# KMO_IO_MV3.net
KiCad netlist of a schematic drawn in EAGLE
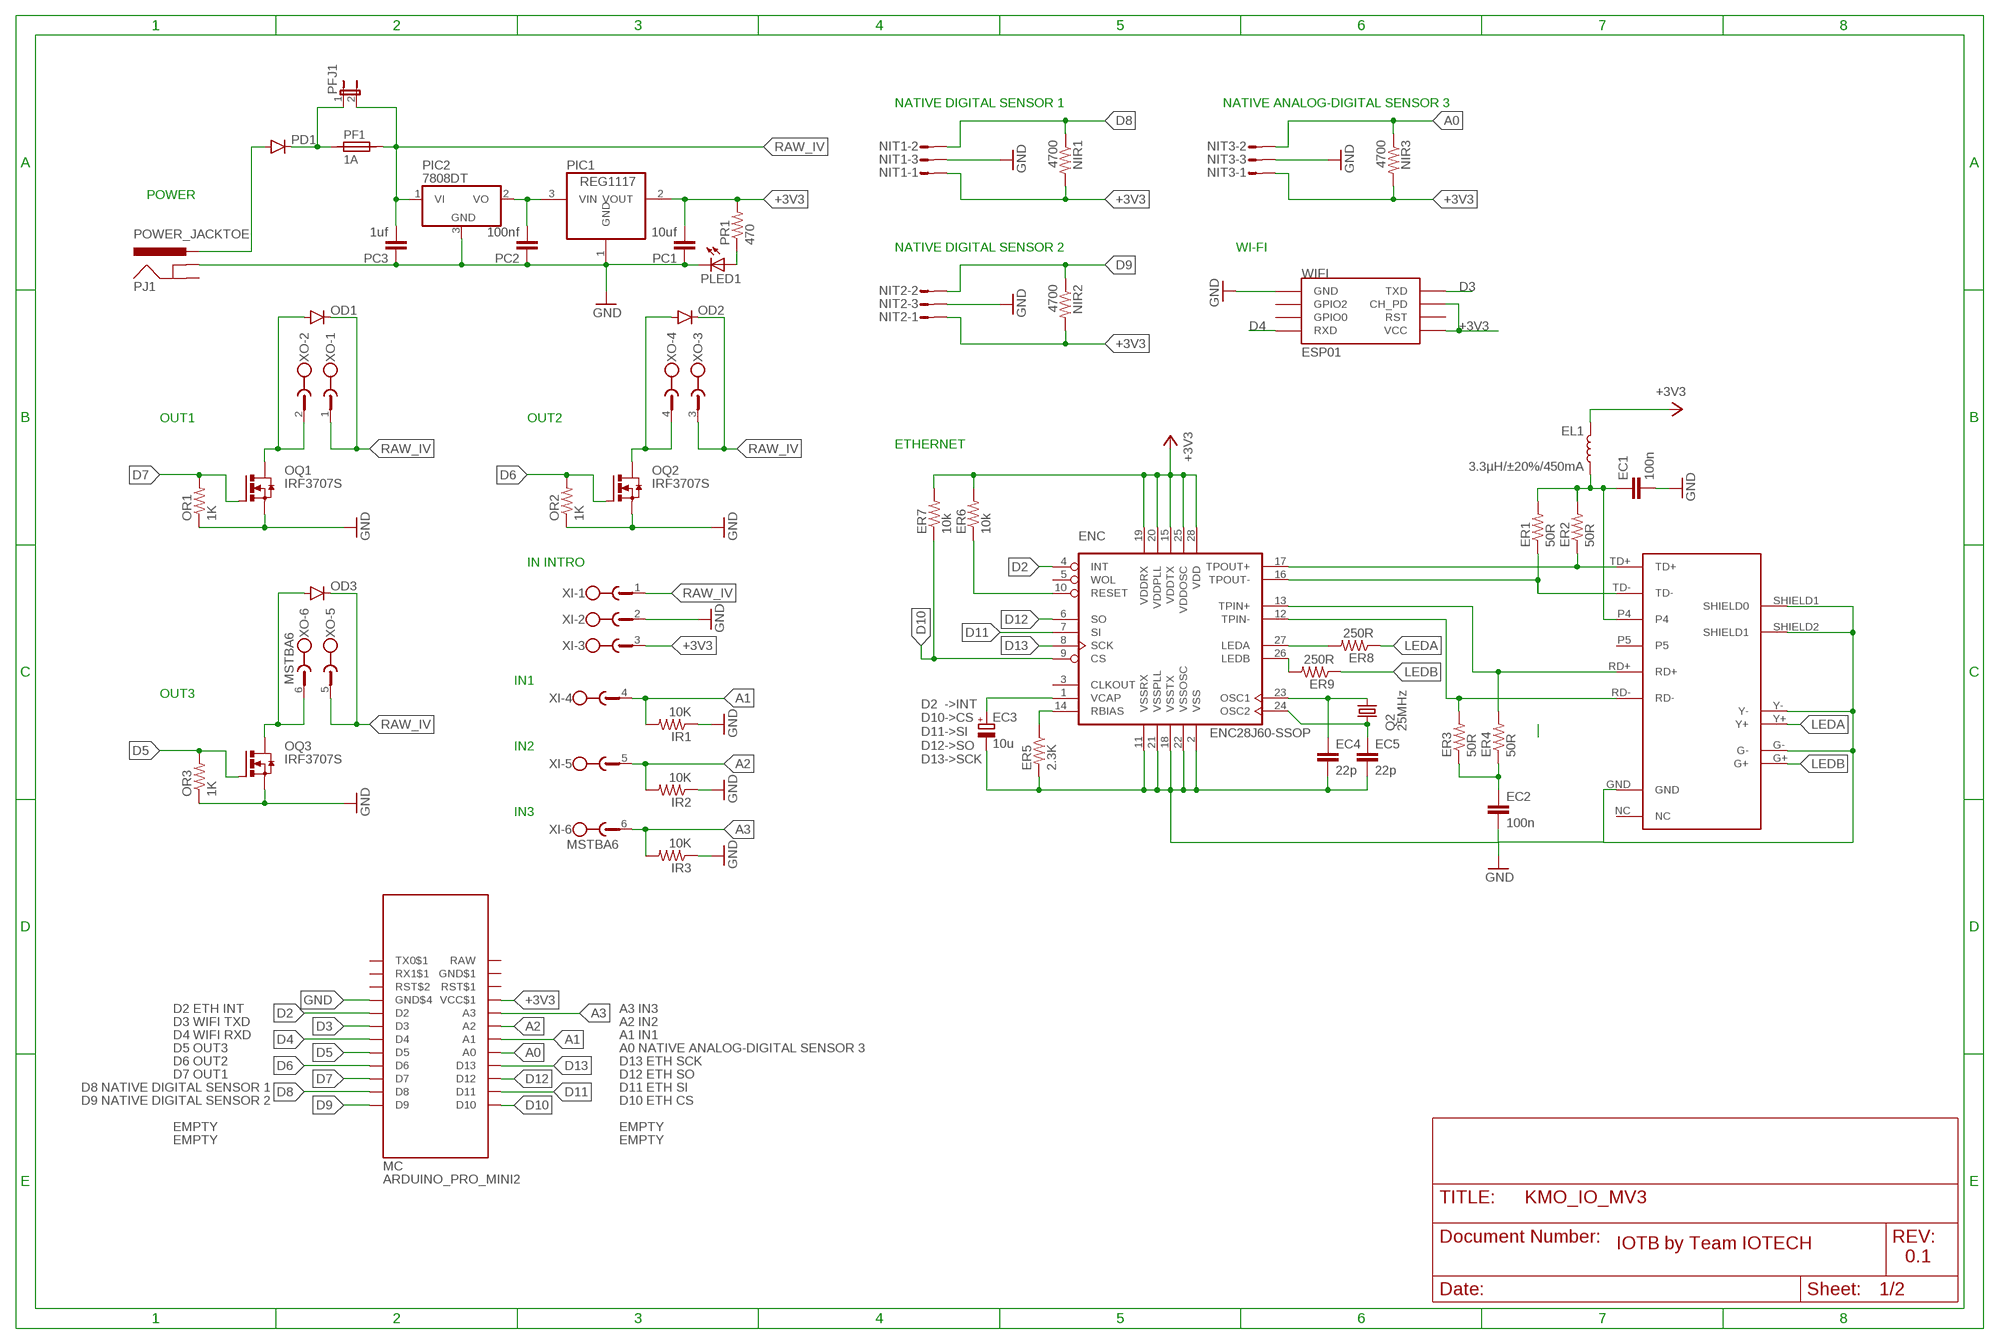
[diagram p0: schematic, sheet 1]
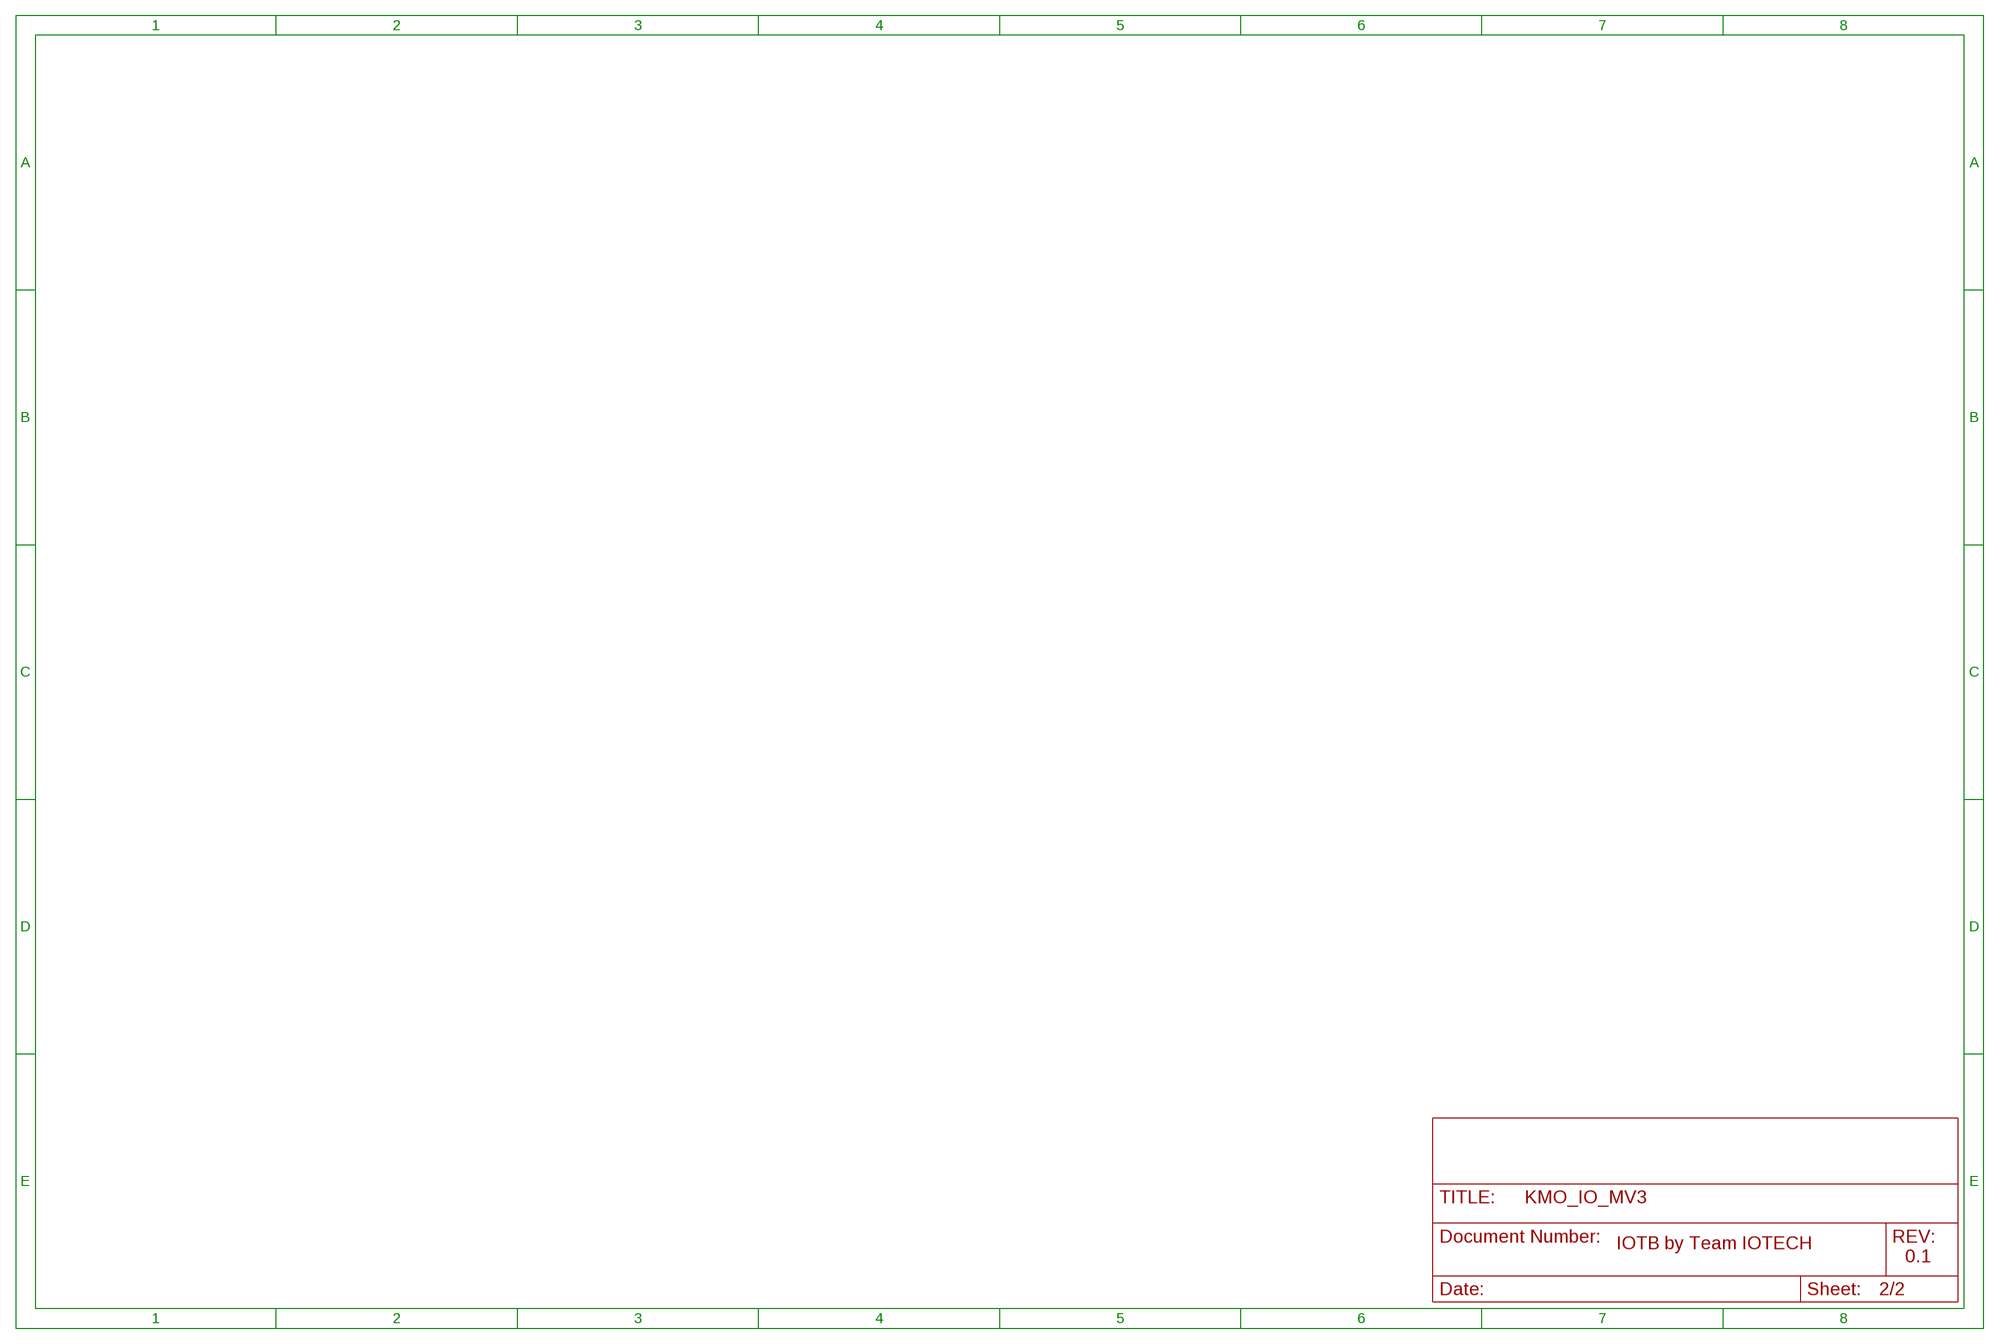
[diagram p1: schematic, sheet 2]

(export (version "E")
  (design (tool "Eeschema 10.0.6"))
  (components
    (comp (ref "EC1")
      (value "100n")
      (footprint "eagle-import:0805")
      (libsource (lib "eagle-import") (part "SparkFun-Passives_CAP0805"))
    )
    (comp (ref "EC2")
      (value "100n")
      (footprint "eagle-import:0805")
      (libsource (lib "eagle-import") (part "SparkFun-Passives_CAP0805"))
    )
    (comp (ref "EC3")
      (value "10u")
      (footprint "eagle-import:SANYO-OSCON_SMD_B6")
      (libsource (lib "eagle-import") (part "CPOL-EUSANYO_SMD_B6"))
    )
    (comp (ref "EC4")
      (value "22p")
      (footprint "eagle-import:0805")
      (libsource (lib "eagle-import") (part "SparkFun-Passives_CAP0805"))
    )
    (comp (ref "EC5")
      (value "22p")
      (footprint "eagle-import:0805")
      (libsource (lib "eagle-import") (part "SparkFun-Passives_CAP0805"))
    )
    (comp (ref "EL1")
      (value "3.3µH/±20%/450mA")
      (footprint "eagle-import:0805")
      (libsource (lib "eagle-import") (part "INDUCTOR-0805-3.3UH"))
    )
    (comp (ref "ENC")
      (value "ENC28J60-SSOP")
      (footprint "eagle-import:SSOP28")
      (libsource (lib "eagle-import") (part "ENC28J60-SSOP"))
    )
    (comp (ref "ER1")
      (value "50R")
      (footprint "eagle-import:0805")
      (libsource (lib "eagle-import") (part "RESISTOR0805-RES"))
    )
    (comp (ref "ER2")
      (value "50R")
      (footprint "eagle-import:0805")
      (libsource (lib "eagle-import") (part "RESISTOR0805-RES"))
    )
    (comp (ref "ER3")
      (value "50R")
      (footprint "eagle-import:0805")
      (libsource (lib "eagle-import") (part "RESISTOR0805-RES"))
    )
    (comp (ref "ER4")
      (value "50R")
      (footprint "eagle-import:0805")
      (libsource (lib "eagle-import") (part "RESISTOR0805-RES"))
    )
    (comp (ref "ER5")
      (value "2.3K")
      (footprint "eagle-import:0805")
      (libsource (lib "eagle-import") (part "RESISTOR0805-RES"))
    )
    (comp (ref "ER6")
      (value "10k")
      (footprint "eagle-import:0805")
      (libsource (lib "eagle-import") (part "RESISTOR0805-RES"))
    )
    (comp (ref "ER7")
      (value "10k")
      (footprint "eagle-import:0805")
      (libsource (lib "eagle-import") (part "RESISTOR0805-RES"))
    )
    (comp (ref "ER8")
      (value "250R")
      (footprint "eagle-import:0805")
      (libsource (lib "eagle-import") (part "RESISTOR0805-RES"))
    )
    (comp (ref "ER9")
      (value "250R")
      (footprint "eagle-import:0805")
      (libsource (lib "eagle-import") (part "RESISTOR0805-RES"))
    )
    (comp (ref "IR1")
      (value "10K")
      (footprint "eagle-import:0805")
      (libsource (lib "eagle-import") (part "RESISTOR0805-RES"))
    )
    (comp (ref "IR2")
      (value "10K")
      (footprint "eagle-import:0805")
      (libsource (lib "eagle-import") (part "RESISTOR0805-RES"))
    )
    (comp (ref "IR3")
      (value "10K")
      (footprint "eagle-import:0805")
      (libsource (lib "eagle-import") (part "RESISTOR0805-RES"))
    )
    (comp (ref "MC")
      (value "ARDUINO_PRO_MINI2")
      (footprint "eagle-import:ARDUINO_PRO_MINI2")
      (libsource (lib "eagle-import") (part "ARDUINO_PRO_MINI2"))
    )
    (comp (ref "NIR1")
      (value "4700")
      (footprint "eagle-import:0805")
      (libsource (lib "eagle-import") (part "RESISTOR0805-RES"))
    )
    (comp (ref "NIR2")
      (value "4700")
      (footprint "eagle-import:0805")
      (libsource (lib "eagle-import") (part "RESISTOR0805-RES"))
    )
    (comp (ref "NIR3")
      (value "4700")
      (footprint "eagle-import:0805")
      (libsource (lib "eagle-import") (part "RESISTOR0805-RES"))
    )
    (comp (ref "NIT1")
      (value "S03P")
      (footprint "eagle-import:S03P")
      (libsource (lib "eagle-import") (part "S03P"))
    )
    (comp (ref "NIT2")
      (value "S03P")
      (footprint "eagle-import:S03P")
      (libsource (lib "eagle-import") (part "S03P"))
    )
    (comp (ref "NIT3")
      (value "S03P")
      (footprint "eagle-import:S03P")
      (libsource (lib "eagle-import") (part "S03P"))
    )
    (comp (ref "OD1")
      (value "DIODESMA")
      (footprint "eagle-import:SMA-DIODE")
      (libsource (lib "eagle-import") (part "DIODESMA"))
    )
    (comp (ref "OD2")
      (value "DIODESMA")
      (footprint "eagle-import:SMA-DIODE")
      (libsource (lib "eagle-import") (part "DIODESMA"))
    )
    (comp (ref "OD3")
      (value "DIODESMA")
      (footprint "eagle-import:SMA-DIODE")
      (libsource (lib "eagle-import") (part "DIODESMA"))
    )
    (comp (ref "OQ1")
      (value "IRF3707S")
      (footprint "eagle-import:D2PACK")
      (libsource (lib "eagle-import") (part "IRF3704S"))
    )
    (comp (ref "OQ2")
      (value "IRF3707S")
      (footprint "eagle-import:D2PACK")
      (libsource (lib "eagle-import") (part "IRF3704S"))
    )
    (comp (ref "OQ3")
      (value "IRF3707S")
      (footprint "eagle-import:D2PACK")
      (libsource (lib "eagle-import") (part "IRF3704S"))
    )
    (comp (ref "OR1")
      (value "1K")
      (footprint "eagle-import:0805")
      (libsource (lib "eagle-import") (part "RESISTOR0805-RES"))
    )
    (comp (ref "OR2")
      (value "1K")
      (footprint "eagle-import:0805")
      (libsource (lib "eagle-import") (part "RESISTOR0805-RES"))
    )
    (comp (ref "OR3")
      (value "1K")
      (footprint "eagle-import:0805")
      (libsource (lib "eagle-import") (part "RESISTOR0805-RES"))
    )
    (comp (ref "PC1")
      (value "10uf")
      (footprint "eagle-import:0805")
      (libsource (lib "eagle-import") (part "CAP0805"))
    )
    (comp (ref "PC2")
      (value "100nf")
      (footprint "eagle-import:0805")
      (libsource (lib "eagle-import") (part "CAP0805"))
    )
    (comp (ref "PC3")
      (value "1uf")
      (footprint "eagle-import:0805")
      (libsource (lib "eagle-import") (part "CAP0805"))
    )
    (comp (ref "PD1")
      (value "DIODESMA")
      (footprint "eagle-import:SMA-DIODE")
      (libsource (lib "eagle-import") (part "DIODESMA"))
    )
    (comp (ref "PF1")
      (value "1A")
      (footprint "eagle-import:1820")
      (libsource (lib "eagle-import") (part "SIBA194600"))
    )
    (comp (ref "PFJ1")
      (value "JP1E")
      (footprint "eagle-import:JP1")
      (libsource (lib "eagle-import") (part "JP1E"))
    )
    (comp (ref "PIC1")
      (value "REG1117")
      (footprint "eagle-import:SOT223")
      (libsource (lib "eagle-import") (part "REG1117"))
    )
    (comp (ref "PIC2")
      (value "7808DT")
      (footprint "eagle-import:TO252")
      (libsource (lib "eagle-import") (part "78DT08"))
    )
    (comp (ref "PJ1")
      (value "POWER_JACKTOE")
      (footprint "eagle-import:POWER_JACK_SMD_OVERPASTE_TOE")
      (libsource (lib "eagle-import") (part "POWER_JACKTOE"))
    )
    (comp (ref "PLED1")
      (value "LEDCHIP-LED0805")
      (footprint "eagle-import:CHIP-LED0805")
      (libsource (lib "eagle-import") (part "LEDCHIP-LED0805"))
    )
    (comp (ref "PR1")
      (value "470")
      (footprint "eagle-import:0805")
      (libsource (lib "eagle-import") (part "RESISTOR0805-RES"))
    )
    (comp (ref "Q2")
      (value "25MHz")
      (footprint "eagle-import:HC49_S")
      (libsource (lib "eagle-import") (part "CRYSTALHC49S"))
    )
    (comp (ref "U$2")
      (value "HR911105A")
      (footprint "eagle-import:RJ45")
      (libsource (lib "eagle-import") (part "HR911105A"))
    )
    (comp (ref "WIFI")
      (value "ESP01")
      (footprint "eagle-import:ESP01")
      (libsource (lib "eagle-import") (part "ESP01"))
    )
    (comp (ref "XI")
      (value "MSTBA6")
      (footprint "eagle-import:MSTBA6")
      (fields (field (name "MF") "FARNELL") (field (name "MPN") "1757284"))
      (libsource (lib "eagle-import") (part "MSTBA6"))
    )
    (comp (ref "XO")
      (value "MSTBA6")
      (footprint "eagle-import:MSTBA6")
      (fields (field (name "MF") "FARNELL") (field (name "MPN") "1757284"))
      (libsource (lib "eagle-import") (part "MSTBA6"))
    )
  )
  (nets
    (net (code "1") (name "+3V3") (class "Default")
      (node (ref "EL1") (pin "1") (pinfunction "1_1") (pintype "passive"))
      (node (ref "ENC") (pin "15") (pinfunction "VDDTX_15") (pintype "power_in"))
      (node (ref "ENC") (pin "19") (pinfunction "VDDRX_19") (pintype "power_in"))
      (node (ref "ENC") (pin "20") (pinfunction "VDDPLL_20") (pintype "power_in"))
      (node (ref "ENC") (pin "25") (pinfunction "VDDOSC_25") (pintype "power_in"))
      (node (ref "ENC") (pin "28") (pinfunction "VDD_28") (pintype "power_in"))
      (node (ref "ER6") (pin "2") (pinfunction "2_2") (pintype "passive"))
      (node (ref "ER7") (pin "2") (pinfunction "2_2") (pintype "passive"))
      (node (ref "MC") (pin "VCC$1") (pinfunction "VCC$1_VCC$1") (pintype "power_in"))
      (node (ref "NIR1") (pin "2") (pinfunction "2_2") (pintype "passive"))
      (node (ref "NIR2") (pin "2") (pinfunction "2_2") (pintype "passive"))
      (node (ref "NIR3") (pin "2") (pinfunction "2_2") (pintype "passive"))
      (node (ref "NIT1") (pin "1") (pinfunction "S_1") (pintype "passive"))
      (node (ref "NIT2") (pin "1") (pinfunction "S_1") (pintype "passive"))
      (node (ref "NIT3") (pin "1") (pinfunction "S_1") (pintype "passive"))
      (node (ref "PC1") (pin "2") (pinfunction "2_2") (pintype "passive"))
      (node (ref "PIC1") (pin "2") (pinfunction "VOUT_2") (pintype "output"))
      (node (ref "PR1") (pin "2") (pinfunction "2_2") (pintype "passive"))
      (node (ref "WIFI") (pin "CH_PD") (pinfunction "CH_PD_CH_PD") (pintype "bidirectional"))
      (node (ref "WIFI") (pin "VCC") (pinfunction "VCC_VCC") (pintype "bidirectional"))
      (node (ref "XI") (pin "3") (pinfunction "1_3") (pintype "passive"))
    )
    (net (code "2") (name "A0") (class "Default")
      (node (ref "MC") (pin "A0") (pinfunction "A0_A0") (pintype "bidirectional"))
      (node (ref "NIR3") (pin "1") (pinfunction "1_1") (pintype "passive"))
      (node (ref "NIT3") (pin "2") (pinfunction "S_2") (pintype "passive"))
    )
    (net (code "3") (name "A1") (class "Default")
      (node (ref "IR1") (pin "2") (pinfunction "2_2") (pintype "passive"))
      (node (ref "MC") (pin "A1") (pinfunction "A1_A1") (pintype "bidirectional"))
      (node (ref "XI") (pin "4") (pinfunction "1_4") (pintype "passive"))
    )
    (net (code "4") (name "A2") (class "Default")
      (node (ref "IR2") (pin "2") (pinfunction "2_2") (pintype "passive"))
      (node (ref "MC") (pin "A2") (pinfunction "A2_A2") (pintype "bidirectional"))
      (node (ref "XI") (pin "5") (pinfunction "1_5") (pintype "passive"))
    )
    (net (code "5") (name "A3") (class "Default")
      (node (ref "IR3") (pin "2") (pinfunction "2_2") (pintype "passive"))
      (node (ref "MC") (pin "A3") (pinfunction "A3_A3") (pintype "bidirectional"))
      (node (ref "XI") (pin "6") (pinfunction "1_6") (pintype "passive"))
    )
    (net (code "6") (name "D2") (class "Default")
      (node (ref "ENC") (pin "4") (pinfunction "INT_4") (pintype "output"))
      (node (ref "MC") (pin "D2") (pinfunction "D2_D2") (pintype "bidirectional"))
    )
    (net (code "7") (name "D3") (class "Default")
      (node (ref "MC") (pin "D3") (pinfunction "D3_D3") (pintype "bidirectional"))
      (node (ref "WIFI") (pin "TX") (pinfunction "TXD_TX") (pintype "bidirectional"))
    )
    (net (code "8") (name "D4") (class "Default")
      (node (ref "MC") (pin "D4") (pinfunction "D4_D4") (pintype "bidirectional"))
      (node (ref "WIFI") (pin "RX") (pinfunction "RXD_RX") (pintype "bidirectional"))
    )
    (net (code "9") (name "D5") (class "Default")
      (node (ref "MC") (pin "D5") (pinfunction "D5_D5") (pintype "bidirectional"))
      (node (ref "OQ3") (pin "1") (pinfunction "G_1") (pintype "passive"))
      (node (ref "OR3") (pin "2") (pinfunction "2_2") (pintype "passive"))
    )
    (net (code "10") (name "D6") (class "Default")
      (node (ref "MC") (pin "D6") (pinfunction "D6_D6") (pintype "bidirectional"))
      (node (ref "OQ2") (pin "1") (pinfunction "G_1") (pintype "passive"))
      (node (ref "OR2") (pin "2") (pinfunction "2_2") (pintype "passive"))
    )
    (net (code "11") (name "D7") (class "Default")
      (node (ref "MC") (pin "D7") (pinfunction "D7_D7") (pintype "bidirectional"))
      (node (ref "OQ1") (pin "1") (pinfunction "G_1") (pintype "passive"))
      (node (ref "OR1") (pin "2") (pinfunction "2_2") (pintype "passive"))
    )
    (net (code "12") (name "D8") (class "Default")
      (node (ref "MC") (pin "D8") (pinfunction "D8_D8") (pintype "bidirectional"))
      (node (ref "NIR1") (pin "1") (pinfunction "1_1") (pintype "passive"))
      (node (ref "NIT1") (pin "2") (pinfunction "S_2") (pintype "passive"))
    )
    (net (code "13") (name "D9") (class "Default")
      (node (ref "MC") (pin "D9") (pinfunction "D9_D9") (pintype "bidirectional"))
      (node (ref "NIR2") (pin "1") (pinfunction "1_1") (pintype "passive"))
      (node (ref "NIT2") (pin "2") (pinfunction "S_2") (pintype "passive"))
    )
    (net (code "14") (name "D10") (class "Default")
      (node (ref "ENC") (pin "9") (pinfunction "CS_9") (pintype "input"))
      (node (ref "ER7") (pin "1") (pinfunction "1_1") (pintype "passive"))
      (node (ref "MC") (pin "D10") (pinfunction "D10_D10") (pintype "bidirectional"))
    )
    (net (code "15") (name "D11") (class "Default")
      (node (ref "ENC") (pin "7") (pinfunction "SI_7") (pintype "input"))
      (node (ref "MC") (pin "D11") (pinfunction "D11_D11") (pintype "bidirectional"))
    )
    (net (code "16") (name "D12") (class "Default")
      (node (ref "ENC") (pin "6") (pinfunction "SO_6") (pintype "output"))
      (node (ref "MC") (pin "D12") (pinfunction "D12_D12") (pintype "bidirectional"))
    )
    (net (code "17") (name "D13") (class "Default")
      (node (ref "ENC") (pin "8") (pinfunction "SCK_8") (pintype "input"))
      (node (ref "MC") (pin "D13") (pinfunction "D13_D13") (pintype "bidirectional"))
    )
    (net (code "18") (name "GND") (class "Default")
      (node (ref "EC1") (pin "2") (pinfunction "2_2") (pintype "passive"))
      (node (ref "EC2") (pin "2") (pinfunction "2_2") (pintype "passive"))
      (node (ref "EC3") (pin "-") (pinfunction "-_-") (pintype "passive"))
      (node (ref "EC4") (pin "2") (pinfunction "2_2") (pintype "passive"))
      (node (ref "EC5") (pin "2") (pinfunction "2_2") (pintype "passive"))
      (node (ref "ENC") (pin "11") (pinfunction "VSSRX_11") (pintype "power_in"))
      (node (ref "ENC") (pin "18") (pinfunction "VSSTX_18") (pintype "power_in"))
      (node (ref "ENC") (pin "2") (pinfunction "VSS_2") (pintype "power_in"))
      (node (ref "ENC") (pin "21") (pinfunction "VSSPLL_21") (pintype "power_in"))
      (node (ref "ENC") (pin "22") (pinfunction "VSSOSC_22") (pintype "power_in"))
      (node (ref "ER5") (pin "2") (pinfunction "2_2") (pintype "passive"))
      (node (ref "IR1") (pin "1") (pinfunction "1_1") (pintype "passive"))
      (node (ref "IR2") (pin "1") (pinfunction "1_1") (pintype "passive"))
      (node (ref "IR3") (pin "1") (pinfunction "1_1") (pintype "passive"))
      (node (ref "MC") (pin "GND$4") (pinfunction "GND$4_GND$4") (pintype "power_in"))
      (node (ref "NIT1") (pin "3") (pinfunction "S_3") (pintype "passive"))
      (node (ref "NIT2") (pin "3") (pinfunction "S_3") (pintype "passive"))
      (node (ref "NIT3") (pin "3") (pinfunction "S_3") (pintype "passive"))
      (node (ref "OQ1") (pin "3") (pinfunction "S_3") (pintype "passive"))
      (node (ref "OQ2") (pin "3") (pinfunction "S_3") (pintype "passive"))
      (node (ref "OQ3") (pin "3") (pinfunction "S_3") (pintype "passive"))
      (node (ref "OR1") (pin "1") (pinfunction "1_1") (pintype "passive"))
      (node (ref "OR2") (pin "1") (pinfunction "1_1") (pintype "passive"))
      (node (ref "OR3") (pin "1") (pinfunction "1_1") (pintype "passive"))
      (node (ref "PC1") (pin "1") (pinfunction "1_1") (pintype "passive"))
      (node (ref "PC2") (pin "1") (pinfunction "1_1") (pintype "passive"))
      (node (ref "PC3") (pin "1") (pinfunction "1_1") (pintype "passive"))
      (node (ref "PIC1") (pin "1") (pinfunction "GND_1") (pintype "power_in"))
      (node (ref "PIC2") (pin "3") (pinfunction "GND_3") (pintype "passive"))
      (node (ref "PJ1") (pin "GND") (pinfunction "GNDBREAK_GND") (pintype "bidirectional"))
      (node (ref "PLED1") (pin "C") (pinfunction "C_C") (pintype "passive"))
      (node (ref "U$2") (pin "G-") (pinfunction "G-_G-") (pintype "bidirectional"))
      (node (ref "U$2") (pin "GND") (pinfunction "GND_GND") (pintype "bidirectional"))
      (node (ref "U$2") (pin "SHIELD1") (pinfunction "SHIELD0_SHIELD1") (pintype "bidirectional"))
      (node (ref "U$2") (pin "SHIELD2") (pinfunction "SHIELD1_SHIELD2") (pintype "bidirectional"))
      (node (ref "U$2") (pin "Y-") (pinfunction "Y-_Y-") (pintype "bidirectional"))
      (node (ref "WIFI") (pin "GND") (pinfunction "GND_GND") (pintype "bidirectional"))
      (node (ref "XI") (pin "2") (pinfunction "1_2") (pintype "passive"))
    )
    (net (code "19") (name "GND$1") (class "Default")
      (node (ref "MC") (pin "GDN$1") (pinfunction "GND$1_GDN$1") (pintype "power_in"))
    )
    (net (code "20") (name "LEDA") (class "Default")
      (node (ref "ER8") (pin "1") (pinfunction "1_1") (pintype "passive"))
      (node (ref "U$2") (pin "Y+") (pinfunction "Y+_Y+") (pintype "bidirectional"))
    )
    (net (code "21") (name "LEDB") (class "Default")
      (node (ref "ER9") (pin "1") (pinfunction "1_1") (pintype "passive"))
      (node (ref "U$2") (pin "G+") (pinfunction "G+_G+") (pintype "bidirectional"))
    )
    (net (code "22") (name "Net-(EC1-Pad1)") (class "Default")
      (node (ref "EC1") (pin "1") (pinfunction "1_1") (pintype "passive"))
      (node (ref "EL1") (pin "2") (pinfunction "2_2") (pintype "passive"))
      (node (ref "ER1") (pin "2") (pinfunction "2_2") (pintype "passive"))
      (node (ref "ER2") (pin "2") (pinfunction "2_2") (pintype "passive"))
      (node (ref "U$2") (pin "P4") (pinfunction "P4_P4") (pintype "bidirectional"))
    )
    (net (code "23") (name "Net-(EC2-Pad1)") (class "Default")
      (node (ref "EC2") (pin "1") (pinfunction "1_1") (pintype "passive"))
      (node (ref "ER3") (pin "1") (pinfunction "1_1") (pintype "passive"))
      (node (ref "ER4") (pin "1") (pinfunction "1_1") (pintype "passive"))
    )
    (net (code "24") (name "Net-(ENC-LEDA)") (class "Default")
      (node (ref "ENC") (pin "27") (pinfunction "LEDA_27") (pintype "output"))
      (node (ref "ER8") (pin "2") (pinfunction "2_2") (pintype "passive"))
    )
    (net (code "25") (name "Net-(ENC-LEDB)") (class "Default")
      (node (ref "ENC") (pin "26") (pinfunction "LEDB_26") (pintype "output"))
      (node (ref "ER9") (pin "2") (pinfunction "2_2") (pintype "passive"))
    )
    (net (code "26") (name "Net-(ENC-OSC1)") (class "Default")
      (node (ref "EC4") (pin "1") (pinfunction "1_1") (pintype "passive"))
      (node (ref "ENC") (pin "23") (pinfunction "OSC1_23") (pintype "input"))
      (node (ref "Q2") (pin "2") (pinfunction "2_2") (pintype "passive"))
    )
    (net (code "27") (name "Net-(ENC-OSC2)") (class "Default")
      (node (ref "EC5") (pin "1") (pinfunction "1_1") (pintype "passive"))
      (node (ref "ENC") (pin "24") (pinfunction "OSC2_24") (pintype "output"))
      (node (ref "Q2") (pin "1") (pinfunction "1_1") (pintype "passive"))
    )
    (net (code "28") (name "Net-(ENC-RBIAS)") (class "Default")
      (node (ref "ENC") (pin "14") (pinfunction "RBIAS_14") (pintype "passive"))
      (node (ref "ER5") (pin "1") (pinfunction "1_1") (pintype "passive"))
    )
    (net (code "29") (name "Net-(ENC-RESET)") (class "Default")
      (node (ref "ENC") (pin "10") (pinfunction "RESET_10") (pintype "input"))
      (node (ref "ER6") (pin "1") (pinfunction "1_1") (pintype "passive"))
    )
    (net (code "30") (name "Net-(ENC-TPIN+)") (class "Default")
      (node (ref "ENC") (pin "13") (pinfunction "TPIN+_13") (pintype "input"))
      (node (ref "ER4") (pin "2") (pinfunction "2_2") (pintype "passive"))
      (node (ref "U$2") (pin "RD+") (pinfunction "RD+_RD+") (pintype "bidirectional"))
    )
    (net (code "31") (name "Net-(ENC-TPIN-)") (class "Default")
      (node (ref "ENC") (pin "12") (pinfunction "TPIN-_12") (pintype "input"))
      (node (ref "ER3") (pin "2") (pinfunction "2_2") (pintype "passive"))
      (node (ref "U$2") (pin "RD-") (pinfunction "RD-_RD-") (pintype "bidirectional"))
    )
    (net (code "32") (name "Net-(ENC-TPOUT+)") (class "Default")
      (node (ref "ENC") (pin "17") (pinfunction "TPOUT+_17") (pintype "output"))
      (node (ref "ER2") (pin "1") (pinfunction "1_1") (pintype "passive"))
      (node (ref "U$2") (pin "TD+") (pinfunction "TD+_TD+") (pintype "bidirectional"))
    )
    (net (code "33") (name "Net-(ENC-TPOUT-)") (class "Default")
      (node (ref "ENC") (pin "16") (pinfunction "TPOUT-_16") (pintype "output"))
      (node (ref "ER1") (pin "1") (pinfunction "1_1") (pintype "passive"))
      (node (ref "U$2") (pin "TD-") (pinfunction "TD-_TD-") (pintype "bidirectional"))
    )
    (net (code "34") (name "Net-(ENC-VCAP)") (class "Default")
      (node (ref "EC3") (pin "+") (pinfunction "+_+") (pintype "passive"))
      (node (ref "ENC") (pin "1") (pinfunction "VCAP_1") (pintype "power_in"))
    )
    (net (code "35") (name "Net-(OQ1-D)") (class "Default")
      (node (ref "OD1") (pin "A") (pinfunction "A_A") (pintype "passive"))
      (node (ref "OQ1") (pin "2") (pinfunction "D_2") (pintype "passive"))
      (node (ref "XO") (pin "2") (pinfunction "1_2") (pintype "passive"))
    )
    (net (code "36") (name "Net-(OQ2-D)") (class "Default")
      (node (ref "OD2") (pin "A") (pinfunction "A_A") (pintype "passive"))
      (node (ref "OQ2") (pin "2") (pinfunction "D_2") (pintype "passive"))
      (node (ref "XO") (pin "4") (pinfunction "1_4") (pintype "passive"))
    )
    (net (code "37") (name "Net-(OQ3-D)") (class "Default")
      (node (ref "OD3") (pin "A") (pinfunction "A_A") (pintype "passive"))
      (node (ref "OQ3") (pin "2") (pinfunction "D_2") (pintype "passive"))
      (node (ref "XO") (pin "6") (pinfunction "1_6") (pintype "passive"))
    )
    (net (code "38") (name "Net-(PD1-PadC)") (class "Default")
      (node (ref "PD1") (pin "C") (pinfunction "C_C") (pintype "passive"))
      (node (ref "PF1") (pin "1") (pinfunction "1_1") (pintype "passive"))
      (node (ref "PFJ1") (pin "1") (pinfunction "1_1") (pintype "passive"))
    )
    (net (code "39") (name "Net-(PIC1-VIN)") (class "Default")
      (node (ref "PC2") (pin "2") (pinfunction "2_2") (pintype "passive"))
      (node (ref "PIC1") (pin "3") (pinfunction "VIN_3") (pintype "input"))
      (node (ref "PIC2") (pin "2") (pinfunction "VO_2") (pintype "passive"))
    )
    (net (code "40") (name "Net-(PJ1-PWR)") (class "Default")
      (node (ref "PD1") (pin "A") (pinfunction "A_A") (pintype "passive"))
      (node (ref "PJ1") (pin "VIN0") (pinfunction "PWR_VIN0") (pintype "bidirectional"))
    )
    (net (code "41") (name "Net-(PLED1-PadA)") (class "Default")
      (node (ref "PLED1") (pin "A") (pinfunction "A_A") (pintype "passive"))
      (node (ref "PR1") (pin "1") (pinfunction "1_1") (pintype "passive"))
    )
    (net (code "42") (name "RAW") (class "Default")
      (node (ref "MC") (pin "RAW") (pinfunction "RAW_RAW") (pintype "power_in"))
    )
    (net (code "43") (name "RAW_IV") (class "Default")
      (node (ref "OD1") (pin "C") (pinfunction "C_C") (pintype "passive"))
      (node (ref "OD2") (pin "C") (pinfunction "C_C") (pintype "passive"))
      (node (ref "OD3") (pin "C") (pinfunction "C_C") (pintype "passive"))
      (node (ref "PC3") (pin "2") (pinfunction "2_2") (pintype "passive"))
      (node (ref "PF1") (pin "2") (pinfunction "2_2") (pintype "passive"))
      (node (ref "PFJ1") (pin "2") (pinfunction "2_2") (pintype "passive"))
      (node (ref "PIC2") (pin "1") (pinfunction "VI_1") (pintype "input"))
      (node (ref "XI") (pin "1") (pinfunction "1_1") (pintype "passive"))
      (node (ref "XO") (pin "1") (pinfunction "1_1") (pintype "passive"))
      (node (ref "XO") (pin "3") (pinfunction "1_3") (pintype "passive"))
      (node (ref "XO") (pin "5") (pinfunction "1_5") (pintype "passive"))
    )
    (net (code "44") (name "unconnected-(ENC-CLKOUT-Pad3)") (class "Default")
      (node (ref "ENC") (pin "3") (pinfunction "CLKOUT_3") (pintype "output"))
    )
    (net (code "45") (name "unconnected-(ENC-WOL-Pad5)") (class "Default")
      (node (ref "ENC") (pin "5") (pinfunction "WOL_5") (pintype "output"))
    )
    (net (code "46") (name "unconnected-(MC-PadRST$1)") (class "Default")
      (node (ref "MC") (pin "RST$1") (pinfunction "RST$1_RST$1") (pintype "input"))
    )
    (net (code "47") (name "unconnected-(MC-PadRST$2)") (class "Default")
      (node (ref "MC") (pin "RST$2") (pinfunction "RST$2_RST$2") (pintype "input"))
    )
    (net (code "48") (name "unconnected-(MC-PadRX1$1)") (class "Default")
      (node (ref "MC") (pin "RX1$1") (pinfunction "RX1$1_RX1$1") (pintype "bidirectional"))
    )
    (net (code "49") (name "unconnected-(MC-PadTX0$1)") (class "Default")
      (node (ref "MC") (pin "TX0$1") (pinfunction "TX0$1_TX0$1") (pintype "bidirectional"))
    )
    (net (code "50") (name "unconnected-(PJ1-GND-PadP$4)") (class "Default")
      (node (ref "PJ1") (pin "P$4") (pinfunction "GND_P$4") (pintype "bidirectional"))
    )
    (net (code "51") (name "unconnected-(U$2-PadNC)") (class "Default")
      (node (ref "U$2") (pin "NC") (pinfunction "NC_NC") (pintype "bidirectional"))
    )
    (net (code "52") (name "unconnected-(U$2-PadP5)") (class "Default")
      (node (ref "U$2") (pin "P5") (pinfunction "P5_P5") (pintype "bidirectional"))
    )
    (net (code "53") (name "unconnected-(WIFI-PadGPIO0)") (class "Default")
      (node (ref "WIFI") (pin "GPIO0") (pinfunction "GPIO0_GPIO0") (pintype "bidirectional"))
    )
    (net (code "54") (name "unconnected-(WIFI-PadGPIO2)") (class "Default")
      (node (ref "WIFI") (pin "GPIO2") (pinfunction "GPIO2_GPIO2") (pintype "bidirectional"))
    )
    (net (code "55") (name "unconnected-(WIFI-PadRST)") (class "Default")
      (node (ref "WIFI") (pin "RST") (pinfunction "RST_RST") (pintype "bidirectional"))
    )
  )
)
